# obc-v2_CM4-FUNCTION.net
KiCad netlist of a schematic drawn in Altium Designer
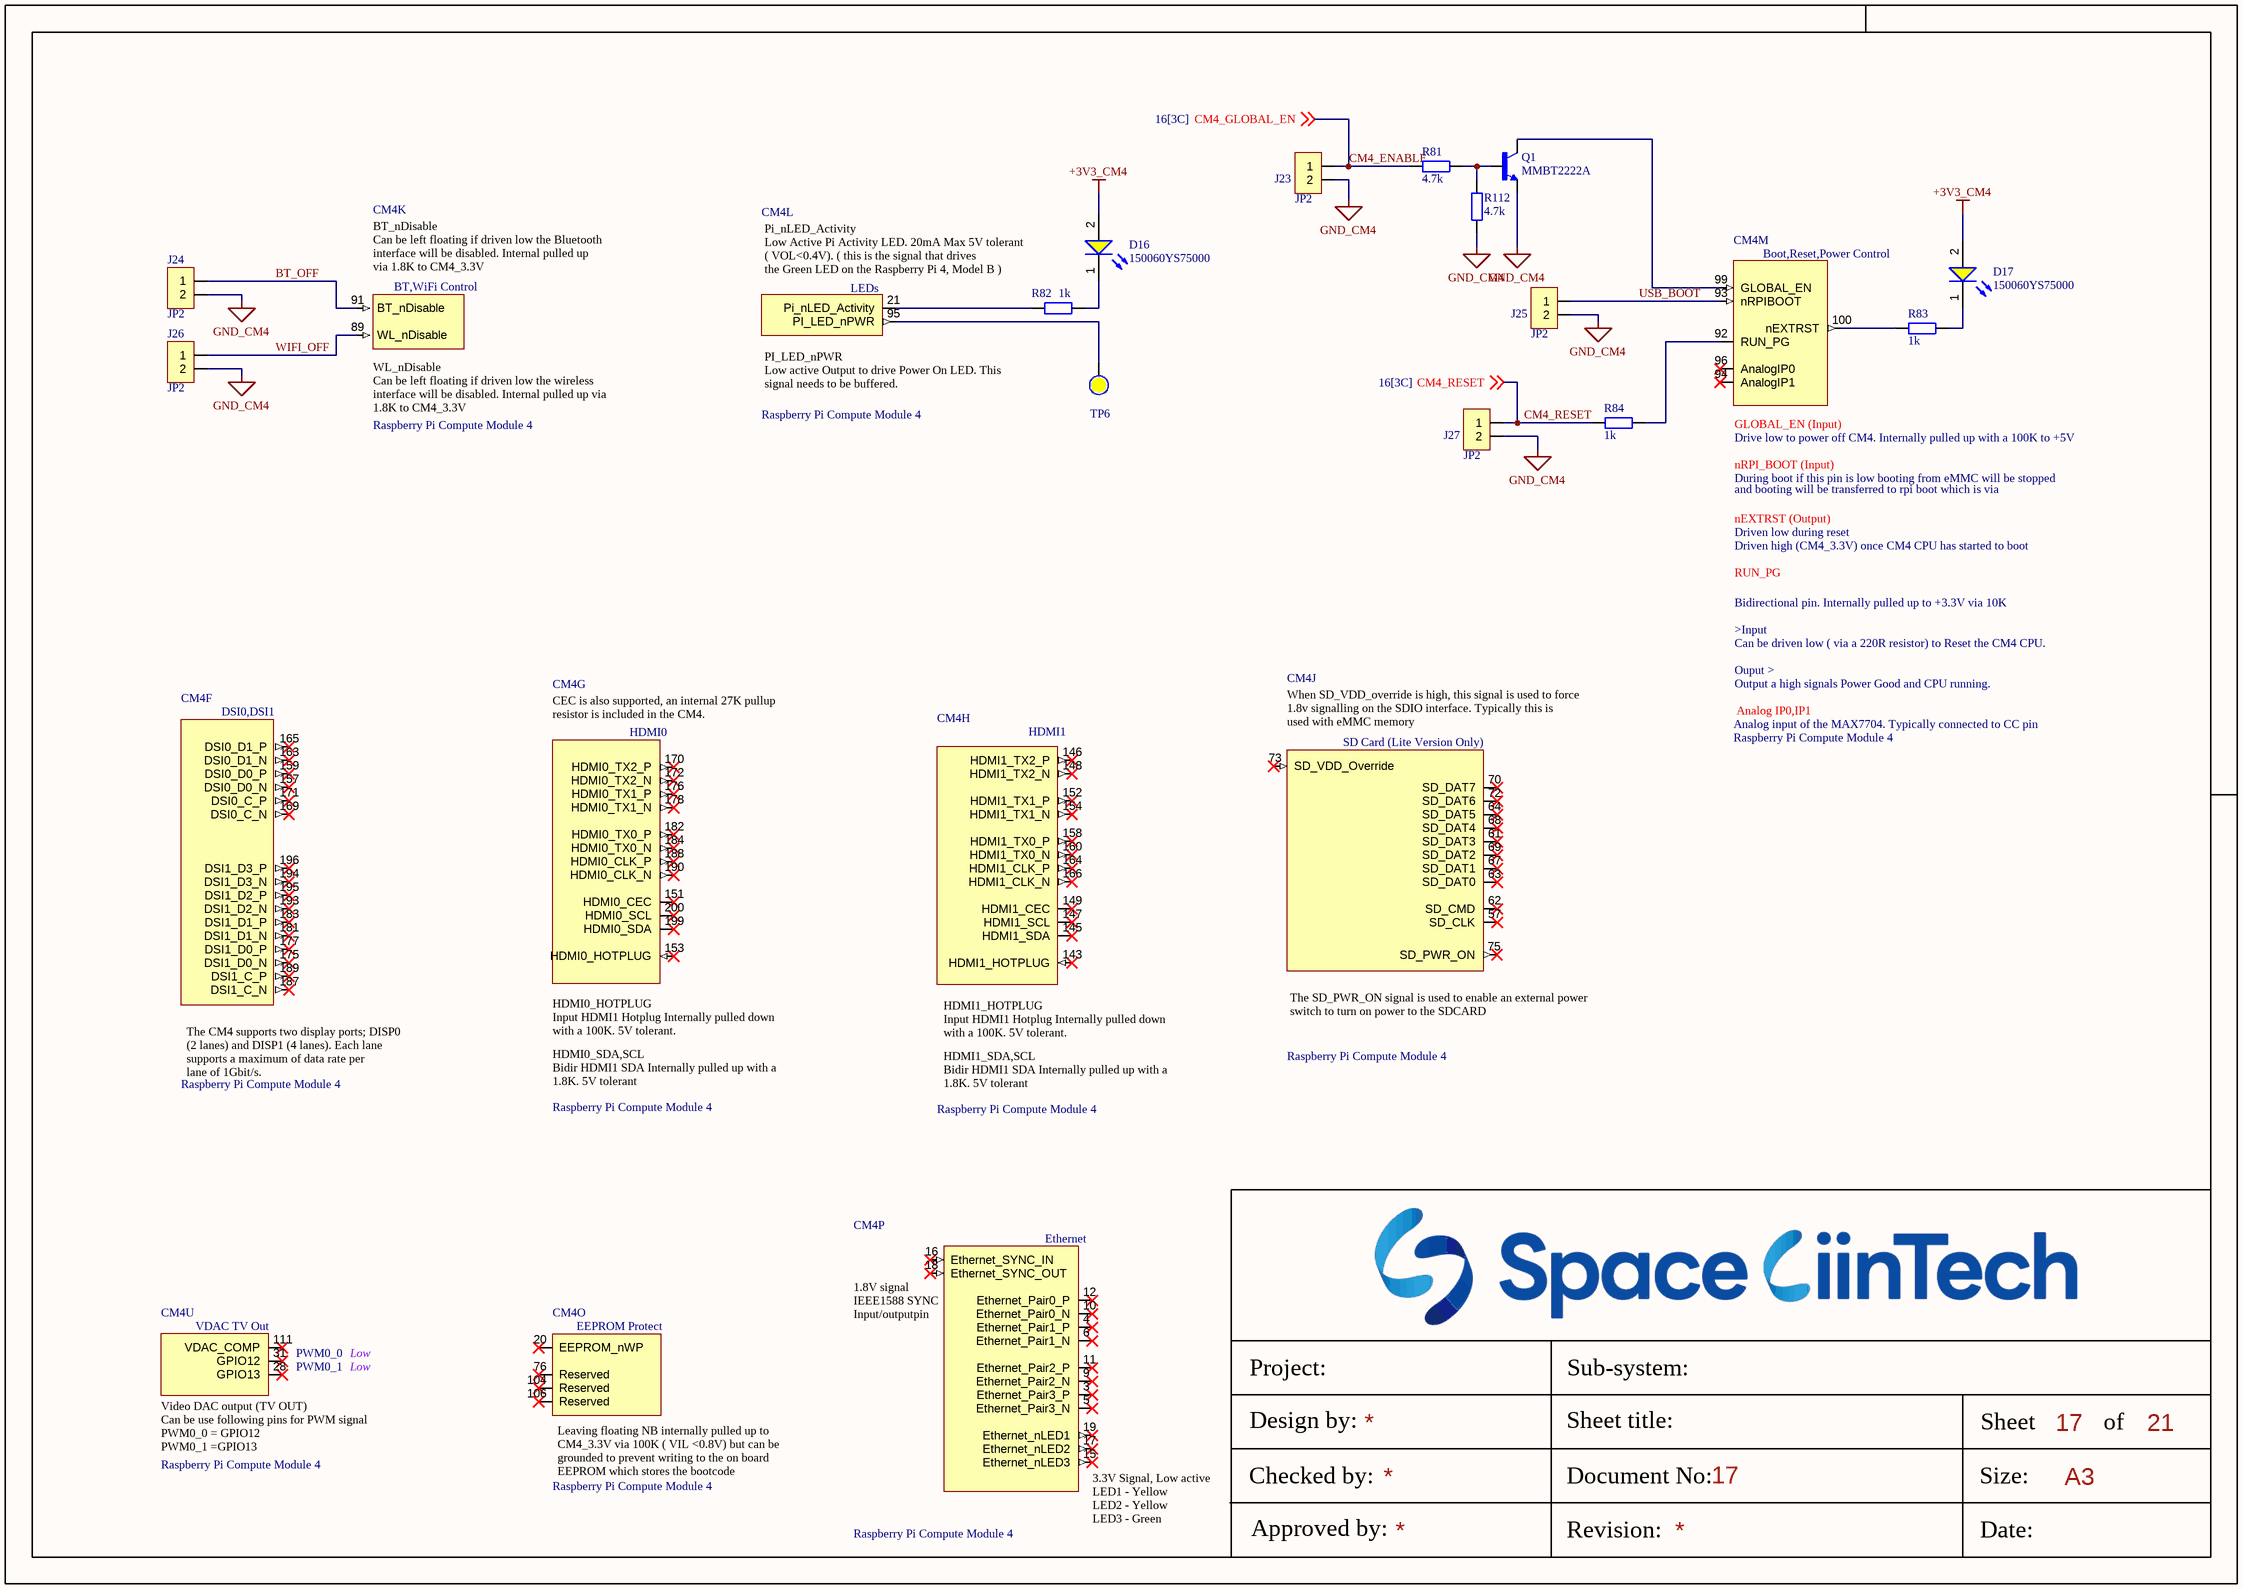
[diagram p0: obc-v2_CM4-FUNCTION.SchDoc]

(export (version "E")
  (design (tool "Eeschema 10.0.6"))
  (components
    (comp (ref "CM4")
      (value "Raspberry Pi Compute Module 4")
      (footprint "CM4-DF40HC(3.0)-100DS-0.4v_3mm_1.5mm")
      (description "Raspberry Pi Compute Module 4 by Amornthep Phunsin")
      (libsource (lib "CM4") (part "CM4"))
    )
    (comp (ref "D16")
      (value "150060YS75000")
      (footprint "WL-SMCW_0603_150060xx75000")
      (description "LED YELLOW CLEAR 0603 SMD")
      (libsource (lib "Altium Content Vault") (part "LED_Yellow_2A-1K"))
    )
    (comp (ref "D17")
      (value "150060YS75000")
      (footprint "WL-SMCW_0603_150060xx75000")
      (description "LED YELLOW CLEAR 0603 SMD")
      (libsource (lib "Altium Content Vault") (part "LED_Yellow_2A-1K"))
    )
    (comp (ref "J23")
      (value "JP2")
      (footprint "JP2-D1T")
      (description "WR-PHD 2.54 mm Angled Socket Header")
      (fields
        (field (name "MANUFACTURER") "Würth Elektronik eiSos GmbH")
        (field (name "PARTNO") "613002143121")
        (field (name "CREATED BY") "Karrer Zheng")
      )
      (libsource (lib "TechMT.VN_Lib") (part "JP2"))
    )
    (comp (ref "J24")
      (value "JP2")
      (footprint "JP2-D1T")
      (description "WR-PHD 2.54 mm Angled Socket Header")
      (fields
        (field (name "MANUFACTURER") "Würth Elektronik eiSos GmbH")
        (field (name "PARTNO") "613002143121")
        (field (name "CREATED BY") "Karrer Zheng")
      )
      (libsource (lib "TechMT.VN_Lib") (part "JP2"))
    )
    (comp (ref "J25")
      (value "JP2")
      (footprint "JP2-D1T")
      (description "WR-PHD 2.54 mm Angled Socket Header")
      (fields
        (field (name "MANUFACTURER") "Würth Elektronik eiSos GmbH")
        (field (name "PARTNO") "613002143121")
        (field (name "CREATED BY") "Karrer Zheng")
      )
      (libsource (lib "TechMT.VN_Lib") (part "JP2"))
    )
    (comp (ref "J26")
      (value "JP2")
      (footprint "JP2-D1T")
      (description "WR-PHD 2.54 mm Angled Socket Header")
      (fields
        (field (name "MANUFACTURER") "Würth Elektronik eiSos GmbH")
        (field (name "PARTNO") "613002143121")
        (field (name "CREATED BY") "Karrer Zheng")
      )
      (libsource (lib "TechMT.VN_Lib") (part "JP2"))
    )
    (comp (ref "J27")
      (value "JP2")
      (footprint "JP2-D1T")
      (description "WR-PHD 2.54 mm Angled Socket Header")
      (fields
        (field (name "MANUFACTURER") "Würth Elektronik eiSos GmbH")
        (field (name "PARTNO") "613002143121")
        (field (name "CREATED BY") "Karrer Zheng")
      )
      (libsource (lib "TechMT.VN_Lib") (part "JP2"))
    )
    (comp (ref "Q1")
      (value "MMBT2222A")
      (footprint "SOT95P240X120-3N")
      (description "BJT, SOT-23, 40V, 600mA, NPN, 0.25W, 150°C")
      (fields (field (name "MF") "Diotec Semiconductor"))
      (libsource (lib "obc_ver2") (part "MMBT2222A"))
    )
    (comp (ref "R81")
      (value "4.7k")
      (footprint "RES_C_1608X60")
      (description "RES")
      (libsource (lib "Altium_Lib_by_KhueNguyenCreator") (part "Tro 0603 1% 10k"))
    )
    (comp (ref "R82")
      (value "1k")
      (footprint "RES_C_1608X60")
      (description "RES")
      (libsource (lib "Altium_Lib_by_KhueNguyenCreator") (part "Tro 0603 1% 10k"))
    )
    (comp (ref "R83")
      (value "1k")
      (footprint "RES_C_1608X60")
      (description "RES")
      (libsource (lib "Altium_Lib_by_KhueNguyenCreator") (part "Tro 0603 1% 10k"))
    )
    (comp (ref "R84")
      (value "1k")
      (footprint "RES_C_1608X60")
      (description "RES")
      (libsource (lib "Altium_Lib_by_KhueNguyenCreator") (part "Tro 0603 1% 10k"))
    )
    (comp (ref "R112")
      (value "4.7k")
      (footprint "RES_C_1608X60")
      (description "RES")
      (libsource (lib "Altium_Lib_by_KhueNguyenCreator") (part "Tro 0603 1% 10k"))
    )
    (comp (ref "TP6")
      (value "~")
      (footprint "Test Point 1 Side")
      (description "Test Point")
      (libsource (lib "BYTECH_HW_LIB_2019 (1)") (part "Test Point"))
    )
  )
  (nets
    (net (code "1") (name "+3V3_CM4") (class "Default")
      (node (ref "D16") (pin "2") (pinfunction "A_2") (pintype "passive"))
      (node (ref "D17") (pin "2") (pinfunction "A_2") (pintype "passive"))
    )
    (net (code "2") (name "/BT_OFF") (class "Default")
      (node (ref "CM4") (pin "91") (pinfunction "BT_nDisable_91") (pintype "input"))
      (node (ref "J24") (pin "1") (pinfunction "1_1") (pintype "passive"))
    )
    (net (code "3") (name "/USB_BOOT") (class "Default")
      (node (ref "CM4") (pin "93") (pinfunction "nRPIBOOT_93") (pintype "input"))
      (node (ref "J25") (pin "1") (pinfunction "1_1") (pintype "passive"))
    )
    (net (code "4") (name "/WIFI_OFF") (class "Default")
      (node (ref "CM4") (pin "89") (pinfunction "WL_nDisable_89") (pintype "input"))
      (node (ref "J26") (pin "1") (pinfunction "1_1") (pintype "passive"))
    )
    (net (code "5") (name "CM4_GLOBAL_EN") (class "Default")
      (node (ref "J23") (pin "1") (pinfunction "1_1") (pintype "passive"))
      (node (ref "R81") (pin "2") (pinfunction "2_2") (pintype "passive"))
    )
    (net (code "6") (name "CM4_RESET") (class "Default")
      (node (ref "J27") (pin "1") (pinfunction "1_1") (pintype "passive"))
      (node (ref "R84") (pin "2") (pinfunction "2_2") (pintype "passive"))
    )
    (net (code "7") (name "GND_CM4") (class "Default")
      (node (ref "J23") (pin "2") (pinfunction "2_2") (pintype "passive"))
      (node (ref "J24") (pin "2") (pinfunction "2_2") (pintype "passive"))
      (node (ref "J25") (pin "2") (pinfunction "2_2") (pintype "passive"))
      (node (ref "J26") (pin "2") (pinfunction "2_2") (pintype "passive"))
      (node (ref "J27") (pin "2") (pinfunction "2_2") (pintype "passive"))
      (node (ref "Q1") (pin "2") (pinfunction "E_2") (pintype "passive"))
      (node (ref "R112") (pin "2") (pinfunction "2_2") (pintype "passive"))
    )
    (net (code "8") (name "Net-(CM4L-PI_LED_nPWR)") (class "Default")
      (node (ref "CM4") (pin "95") (pinfunction "PI_LED_nPWR_95") (pintype "output"))
      (node (ref "TP6") (pin "0") (pinfunction "0_0") (pintype "passive"))
    )
    (net (code "9") (name "Net-(CM4L-Pi_nLED_Activity)") (class "Default")
      (node (ref "CM4") (pin "21") (pinfunction "Pi_nLED_Activity_21") (pintype "open_collector"))
      (node (ref "R82") (pin "2") (pinfunction "2_2") (pintype "passive"))
    )
    (net (code "10") (name "Net-(CM4M-GLOBAL_EN)") (class "Default")
      (node (ref "CM4") (pin "99") (pinfunction "GLOBAL_EN_99") (pintype "input"))
      (node (ref "Q1") (pin "3") (pinfunction "C_3") (pintype "passive"))
    )
    (net (code "11") (name "Net-(CM4M-RUN_PG)") (class "Default")
      (node (ref "CM4") (pin "92") (pinfunction "RUN_PG_92") (pintype "passive"))
      (node (ref "R84") (pin "1") (pinfunction "1_1") (pintype "passive"))
    )
    (net (code "12") (name "Net-(CM4M-nEXTRST)") (class "Default")
      (node (ref "CM4") (pin "100") (pinfunction "nEXTRST_100") (pintype "output"))
      (node (ref "R83") (pin "2") (pinfunction "2_2") (pintype "passive"))
    )
    (net (code "13") (name "Net-(D16-K)") (class "Default")
      (node (ref "D16") (pin "1") (pinfunction "K_1") (pintype "passive"))
      (node (ref "R82") (pin "1") (pinfunction "1_1") (pintype "passive"))
    )
    (net (code "14") (name "Net-(D17-K)") (class "Default")
      (node (ref "D17") (pin "1") (pinfunction "K_1") (pintype "passive"))
      (node (ref "R83") (pin "1") (pinfunction "1_1") (pintype "passive"))
    )
    (net (code "15") (name "Net-(Q1-B)") (class "Default")
      (node (ref "Q1") (pin "1") (pinfunction "B_1") (pintype "passive"))
      (node (ref "R112") (pin "1") (pinfunction "1_1") (pintype "passive"))
      (node (ref "R81") (pin "1") (pinfunction "1_1") (pintype "passive"))
    )
    (net (code "16") (name "unconnected-(CM4F-DSI0_C_N-Pad169)") (class "Default")
      (node (ref "CM4") (pin "169") (pinfunction "DSI0_C_N_169") (pintype "output+no_connect"))
    )
    (net (code "17") (name "unconnected-(CM4F-DSI0_C_P-Pad171)") (class "Default")
      (node (ref "CM4") (pin "171") (pinfunction "DSI0_C_P_171") (pintype "output+no_connect"))
    )
    (net (code "18") (name "unconnected-(CM4F-DSI0_D0_N-Pad157)") (class "Default")
      (node (ref "CM4") (pin "157") (pinfunction "DSI0_D0_N_157") (pintype "output+no_connect"))
    )
    (net (code "19") (name "unconnected-(CM4F-DSI0_D0_P-Pad159)") (class "Default")
      (node (ref "CM4") (pin "159") (pinfunction "DSI0_D0_P_159") (pintype "output+no_connect"))
    )
    (net (code "20") (name "unconnected-(CM4F-DSI0_D1_N-Pad163)") (class "Default")
      (node (ref "CM4") (pin "163") (pinfunction "DSI0_D1_N_163") (pintype "output+no_connect"))
    )
    (net (code "21") (name "unconnected-(CM4F-DSI0_D1_P-Pad165)") (class "Default")
      (node (ref "CM4") (pin "165") (pinfunction "DSI0_D1_P_165") (pintype "output+no_connect"))
    )
    (net (code "22") (name "unconnected-(CM4F-DSI1_C_N-Pad187)") (class "Default")
      (node (ref "CM4") (pin "187") (pinfunction "DSI1_C_N_187") (pintype "output+no_connect"))
    )
    (net (code "23") (name "unconnected-(CM4F-DSI1_C_P-Pad189)") (class "Default")
      (node (ref "CM4") (pin "189") (pinfunction "DSI1_C_P_189") (pintype "output+no_connect"))
    )
    (net (code "24") (name "unconnected-(CM4F-DSI1_D0_N-Pad175)") (class "Default")
      (node (ref "CM4") (pin "175") (pinfunction "DSI1_D0_N_175") (pintype "output+no_connect"))
    )
    (net (code "25") (name "unconnected-(CM4F-DSI1_D0_P-Pad177)") (class "Default")
      (node (ref "CM4") (pin "177") (pinfunction "DSI1_D0_P_177") (pintype "output+no_connect"))
    )
    (net (code "26") (name "unconnected-(CM4F-DSI1_D1_N-Pad181)") (class "Default")
      (node (ref "CM4") (pin "181") (pinfunction "DSI1_D1_N_181") (pintype "output+no_connect"))
    )
    (net (code "27") (name "unconnected-(CM4F-DSI1_D1_P-Pad183)") (class "Default")
      (node (ref "CM4") (pin "183") (pinfunction "DSI1_D1_P_183") (pintype "output+no_connect"))
    )
    (net (code "28") (name "unconnected-(CM4F-DSI1_D2_N-Pad193)") (class "Default")
      (node (ref "CM4") (pin "193") (pinfunction "DSI1_D2_N_193") (pintype "output+no_connect"))
    )
    (net (code "29") (name "unconnected-(CM4F-DSI1_D2_P-Pad195)") (class "Default")
      (node (ref "CM4") (pin "195") (pinfunction "DSI1_D2_P_195") (pintype "output+no_connect"))
    )
    (net (code "30") (name "unconnected-(CM4F-DSI1_D3_N-Pad194)") (class "Default")
      (node (ref "CM4") (pin "194") (pinfunction "DSI1_D3_N_194") (pintype "output+no_connect"))
    )
    (net (code "31") (name "unconnected-(CM4F-DSI1_D3_P-Pad196)") (class "Default")
      (node (ref "CM4") (pin "196") (pinfunction "DSI1_D3_P_196") (pintype "output+no_connect"))
    )
    (net (code "32") (name "unconnected-(CM4G-HDMI0_CEC-Pad151)") (class "Default")
      (node (ref "CM4") (pin "151") (pinfunction "HDMI0_CEC_151") (pintype "open_collector+no_connect"))
    )
    (net (code "33") (name "unconnected-(CM4G-HDMI0_CLK_N-Pad190)") (class "Default")
      (node (ref "CM4") (pin "190") (pinfunction "HDMI0_CLK_N_190") (pintype "output+no_connect"))
    )
    (net (code "34") (name "unconnected-(CM4G-HDMI0_CLK_P-Pad188)") (class "Default")
      (node (ref "CM4") (pin "188") (pinfunction "HDMI0_CLK_P_188") (pintype "output+no_connect"))
    )
    (net (code "35") (name "unconnected-(CM4G-HDMI0_HOTPLUG-Pad153)") (class "Default")
      (node (ref "CM4") (pin "153") (pinfunction "HDMI0_HOTPLUG_153") (pintype "input+no_connect"))
    )
    (net (code "36") (name "unconnected-(CM4G-HDMI0_SCL-Pad200)") (class "Default")
      (node (ref "CM4") (pin "200") (pinfunction "HDMI0_SCL_200") (pintype "open_collector+no_connect"))
    )
    (net (code "37") (name "unconnected-(CM4G-HDMI0_SDA-Pad199)") (class "Default")
      (node (ref "CM4") (pin "199") (pinfunction "HDMI0_SDA_199") (pintype "bidirectional+no_connect"))
    )
    (net (code "38") (name "unconnected-(CM4G-HDMI0_TX0_N-Pad184)") (class "Default")
      (node (ref "CM4") (pin "184") (pinfunction "HDMI0_TX0_N_184") (pintype "output+no_connect"))
    )
    (net (code "39") (name "unconnected-(CM4G-HDMI0_TX0_P-Pad182)") (class "Default")
      (node (ref "CM4") (pin "182") (pinfunction "HDMI0_TX0_P_182") (pintype "output+no_connect"))
    )
    (net (code "40") (name "unconnected-(CM4G-HDMI0_TX1_N-Pad178)") (class "Default")
      (node (ref "CM4") (pin "178") (pinfunction "HDMI0_TX1_N_178") (pintype "output+no_connect"))
    )
    (net (code "41") (name "unconnected-(CM4G-HDMI0_TX1_P-Pad176)") (class "Default")
      (node (ref "CM4") (pin "176") (pinfunction "HDMI0_TX1_P_176") (pintype "output+no_connect"))
    )
    (net (code "42") (name "unconnected-(CM4G-HDMI0_TX2_N-Pad172)") (class "Default")
      (node (ref "CM4") (pin "172") (pinfunction "HDMI0_TX2_N_172") (pintype "output+no_connect"))
    )
    (net (code "43") (name "unconnected-(CM4G-HDMI0_TX2_P-Pad170)") (class "Default")
      (node (ref "CM4") (pin "170") (pinfunction "HDMI0_TX2_P_170") (pintype "output+no_connect"))
    )
    (net (code "44") (name "unconnected-(CM4H-HDMI1_CEC-Pad149)") (class "Default")
      (node (ref "CM4") (pin "149") (pinfunction "HDMI1_CEC_149") (pintype "open_collector+no_connect"))
    )
    (net (code "45") (name "unconnected-(CM4H-HDMI1_CLK_N-Pad166)") (class "Default")
      (node (ref "CM4") (pin "166") (pinfunction "HDMI1_CLK_N_166") (pintype "output+no_connect"))
    )
    (net (code "46") (name "unconnected-(CM4H-HDMI1_CLK_P-Pad164)") (class "Default")
      (node (ref "CM4") (pin "164") (pinfunction "HDMI1_CLK_P_164") (pintype "output+no_connect"))
    )
    (net (code "47") (name "unconnected-(CM4H-HDMI1_HOTPLUG-Pad143)") (class "Default")
      (node (ref "CM4") (pin "143") (pinfunction "HDMI1_HOTPLUG_143") (pintype "input+no_connect"))
    )
    (net (code "48") (name "unconnected-(CM4H-HDMI1_SCL-Pad147)") (class "Default")
      (node (ref "CM4") (pin "147") (pinfunction "HDMI1_SCL_147") (pintype "open_collector+no_connect"))
    )
    (net (code "49") (name "unconnected-(CM4H-HDMI1_SDA-Pad145)") (class "Default")
      (node (ref "CM4") (pin "145") (pinfunction "HDMI1_SDA_145") (pintype "bidirectional+no_connect"))
    )
    (net (code "50") (name "unconnected-(CM4H-HDMI1_TX0_N-Pad160)") (class "Default")
      (node (ref "CM4") (pin "160") (pinfunction "HDMI1_TX0_N_160") (pintype "output+no_connect"))
    )
    (net (code "51") (name "unconnected-(CM4H-HDMI1_TX0_P-Pad158)") (class "Default")
      (node (ref "CM4") (pin "158") (pinfunction "HDMI1_TX0_P_158") (pintype "output+no_connect"))
    )
    (net (code "52") (name "unconnected-(CM4H-HDMI1_TX1_N-Pad154)") (class "Default")
      (node (ref "CM4") (pin "154") (pinfunction "HDMI1_TX1_N_154") (pintype "output+no_connect"))
    )
    (net (code "53") (name "unconnected-(CM4H-HDMI1_TX1_P-Pad152)") (class "Default")
      (node (ref "CM4") (pin "152") (pinfunction "HDMI1_TX1_P_152") (pintype "output+no_connect"))
    )
    (net (code "54") (name "unconnected-(CM4H-HDMI1_TX2_N-Pad148)") (class "Default")
      (node (ref "CM4") (pin "148") (pinfunction "HDMI1_TX2_N_148") (pintype "output+no_connect"))
    )
    (net (code "55") (name "unconnected-(CM4H-HDMI1_TX2_P-Pad146)") (class "Default")
      (node (ref "CM4") (pin "146") (pinfunction "HDMI1_TX2_P_146") (pintype "output+no_connect"))
    )
    (net (code "56") (name "unconnected-(CM4J-SD_CLK-Pad57)") (class "Default")
      (node (ref "CM4") (pin "57") (pinfunction "SD_CLK_57") (pintype "passive+no_connect"))
    )
    (net (code "57") (name "unconnected-(CM4J-SD_CMD-Pad62)") (class "Default")
      (node (ref "CM4") (pin "62") (pinfunction "SD_CMD_62") (pintype "passive+no_connect"))
    )
    (net (code "58") (name "unconnected-(CM4J-SD_DAT0-Pad63)") (class "Default")
      (node (ref "CM4") (pin "63") (pinfunction "SD_DAT0_63") (pintype "passive+no_connect"))
    )
    (net (code "59") (name "unconnected-(CM4J-SD_DAT1-Pad67)") (class "Default")
      (node (ref "CM4") (pin "67") (pinfunction "SD_DAT1_67") (pintype "passive+no_connect"))
    )
    (net (code "60") (name "unconnected-(CM4J-SD_DAT2-Pad69)") (class "Default")
      (node (ref "CM4") (pin "69") (pinfunction "SD_DAT2_69") (pintype "passive+no_connect"))
    )
    (net (code "61") (name "unconnected-(CM4J-SD_DAT3-Pad61)") (class "Default")
      (node (ref "CM4") (pin "61") (pinfunction "SD_DAT3_61") (pintype "passive+no_connect"))
    )
    (net (code "62") (name "unconnected-(CM4J-SD_DAT4-Pad68)") (class "Default")
      (node (ref "CM4") (pin "68") (pinfunction "SD_DAT4_68") (pintype "passive"))
    )
    (net (code "63") (name "unconnected-(CM4J-SD_DAT5-Pad64)") (class "Default")
      (node (ref "CM4") (pin "64") (pinfunction "SD_DAT5_64") (pintype "passive+no_connect"))
    )
    (net (code "64") (name "unconnected-(CM4J-SD_DAT6-Pad72)") (class "Default")
      (node (ref "CM4") (pin "72") (pinfunction "SD_DAT6_72") (pintype "passive+no_connect"))
    )
    (net (code "65") (name "unconnected-(CM4J-SD_DAT7-Pad70)") (class "Default")
      (node (ref "CM4") (pin "70") (pinfunction "SD_DAT7_70") (pintype "passive+no_connect"))
    )
    (net (code "66") (name "unconnected-(CM4J-SD_PWR_ON-Pad75)") (class "Default")
      (node (ref "CM4") (pin "75") (pinfunction "SD_PWR_ON_75") (pintype "output+no_connect"))
    )
    (net (code "67") (name "unconnected-(CM4J-SD_VDD_Override-Pad73)") (class "Default")
      (node (ref "CM4") (pin "73") (pinfunction "SD_VDD_Override_73") (pintype "input+no_connect"))
    )
    (net (code "68") (name "unconnected-(CM4M-AnalogIP0-Pad96)") (class "Default")
      (node (ref "CM4") (pin "96") (pinfunction "AnalogIP0_96") (pintype "passive+no_connect"))
    )
    (net (code "69") (name "unconnected-(CM4M-AnalogIP1-Pad94)") (class "Default")
      (node (ref "CM4") (pin "94") (pinfunction "AnalogIP1_94") (pintype "passive+no_connect"))
    )
    (net (code "70") (name "unconnected-(CM4O-EEPROM_nWP-Pad20)") (class "Default")
      (node (ref "CM4") (pin "20") (pinfunction "EEPROM_nWP_20") (pintype "passive+no_connect"))
    )
    (net (code "71") (name "unconnected-(CM4O-Reserved-Pad76)") (class "Default")
      (node (ref "CM4") (pin "76") (pinfunction "Reserved_76") (pintype "passive+no_connect"))
    )
    (net (code "72") (name "unconnected-(CM4O-Reserved-Pad104)") (class "Default")
      (node (ref "CM4") (pin "104") (pinfunction "Reserved_104") (pintype "passive+no_connect"))
    )
    (net (code "73") (name "unconnected-(CM4O-Reserved-Pad106)") (class "Default")
      (node (ref "CM4") (pin "106") (pinfunction "Reserved_106") (pintype "passive+no_connect"))
    )
    (net (code "74") (name "unconnected-(CM4P-Ethernet_Pair0_N-Pad10)") (class "Default")
      (node (ref "CM4") (pin "10") (pinfunction "Ethernet_Pair0_N_10") (pintype "passive+no_connect"))
    )
    (net (code "75") (name "unconnected-(CM4P-Ethernet_Pair0_P-Pad12)") (class "Default")
      (node (ref "CM4") (pin "12") (pinfunction "Ethernet_Pair0_P_12") (pintype "passive+no_connect"))
    )
    (net (code "76") (name "unconnected-(CM4P-Ethernet_Pair1_N-Pad6)") (class "Default")
      (node (ref "CM4") (pin "6") (pinfunction "Ethernet_Pair1_N_6") (pintype "passive+no_connect"))
    )
    (net (code "77") (name "unconnected-(CM4P-Ethernet_Pair1_P-Pad4)") (class "Default")
      (node (ref "CM4") (pin "4") (pinfunction "Ethernet_Pair1_P_4") (pintype "passive+no_connect"))
    )
    (net (code "78") (name "unconnected-(CM4P-Ethernet_Pair2_N-Pad9)") (class "Default")
      (node (ref "CM4") (pin "9") (pinfunction "Ethernet_Pair2_N_9") (pintype "passive+no_connect"))
    )
    (net (code "79") (name "unconnected-(CM4P-Ethernet_Pair2_P-Pad11)") (class "Default")
      (node (ref "CM4") (pin "11") (pinfunction "Ethernet_Pair2_P_11") (pintype "passive+no_connect"))
    )
    (net (code "80") (name "unconnected-(CM4P-Ethernet_Pair3_N-Pad5)") (class "Default")
      (node (ref "CM4") (pin "5") (pinfunction "Ethernet_Pair3_N_5") (pintype "passive+no_connect"))
    )
    (net (code "81") (name "unconnected-(CM4P-Ethernet_Pair3_P-Pad3)") (class "Default")
      (node (ref "CM4") (pin "3") (pinfunction "Ethernet_Pair3_P_3") (pintype "passive+no_connect"))
    )
    (net (code "82") (name "unconnected-(CM4P-Ethernet_SYNC_IN-Pad16)") (class "Default")
      (node (ref "CM4") (pin "16") (pinfunction "Ethernet_SYNC_IN_16") (pintype "input+no_connect"))
    )
    (net (code "83") (name "unconnected-(CM4P-Ethernet_SYNC_OUT-Pad18)") (class "Default")
      (node (ref "CM4") (pin "18") (pinfunction "Ethernet_SYNC_OUT_18") (pintype "input+no_connect"))
    )
    (net (code "84") (name "unconnected-(CM4P-Ethernet_nLED1-Pad19)") (class "Default")
      (node (ref "CM4") (pin "19") (pinfunction "Ethernet_nLED1_19") (pintype "output+no_connect"))
    )
    (net (code "85") (name "unconnected-(CM4P-Ethernet_nLED2-Pad17)") (class "Default")
      (node (ref "CM4") (pin "17") (pinfunction "Ethernet_nLED2_17") (pintype "output+no_connect"))
    )
    (net (code "86") (name "unconnected-(CM4P-Ethernet_nLED3-Pad15)") (class "Default")
      (node (ref "CM4") (pin "15") (pinfunction "Ethernet_nLED3_15") (pintype "output+no_connect"))
    )
    (net (code "87") (name "unconnected-(CM4U-GPIO12-Pad31)") (class "Default")
      (node (ref "CM4") (pin "31") (pinfunction "GPIO12_31") (pintype "passive+no_connect"))
    )
    (net (code "88") (name "unconnected-(CM4U-GPIO13-Pad28)") (class "Default")
      (node (ref "CM4") (pin "28") (pinfunction "GPIO13_28") (pintype "passive+no_connect"))
    )
    (net (code "89") (name "unconnected-(CM4U-VDAC_COMP-Pad111)") (class "Default")
      (node (ref "CM4") (pin "111") (pinfunction "VDAC_COMP_111") (pintype "passive+no_connect"))
    )
  )
)
